# v1_control.net
KiCad netlist of a schematic drawn in Altium Designer
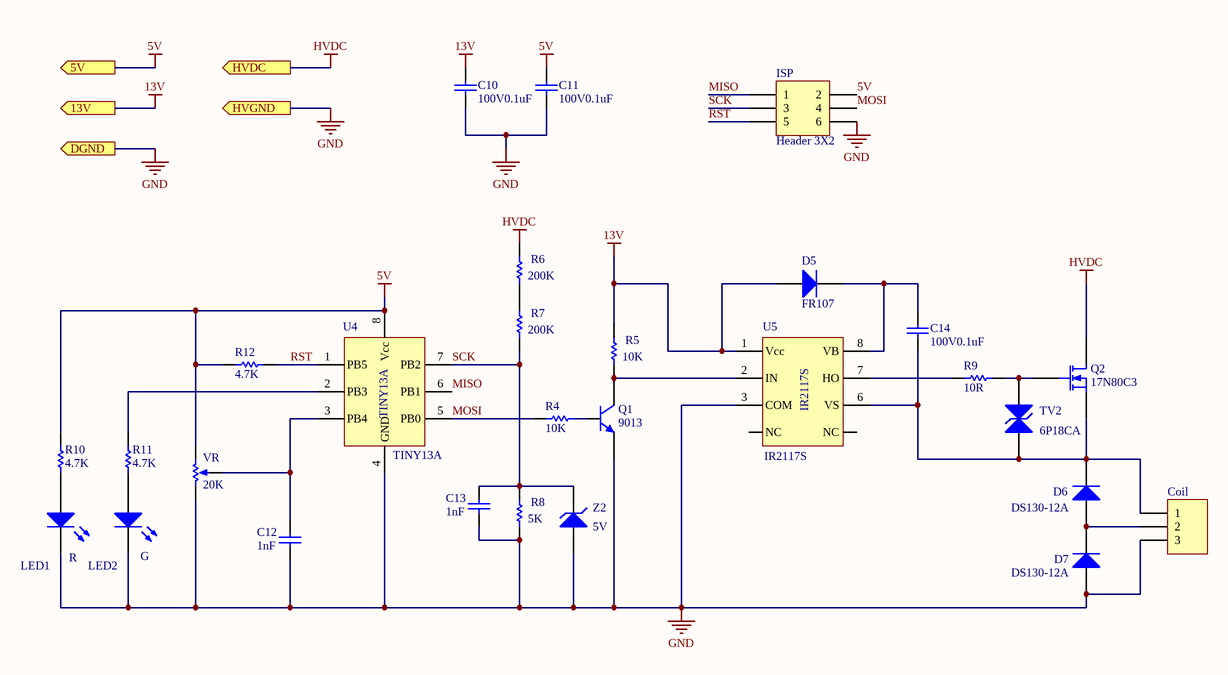
[diagram p0: v1_control.SCHDOC]

(export (version "E")
  (design (tool "Eeschema 10.0.6"))
  (components
    (comp (ref "C10")
      (value "100V0.1uF")
      (footprint "CAP6")
      (description "Capacitor")
      (fields (field (name "PUBLISHER") "Altium Limited"))
      (libsource (lib "magcontrol") (part "Cap"))
    )
    (comp (ref "C11")
      (value "100V0.1uF")
      (footprint "CAP6")
      (description "Capacitor")
      (fields (field (name "PUBLISHER") "Altium Limited"))
      (libsource (lib "magcontrol") (part "Cap"))
    )
    (comp (ref "C12")
      (value "1nF")
      (footprint "CAP6")
      (description "Capacitor")
      (fields (field (name "PUBLISHER") "Altium Limited"))
      (libsource (lib "magcontrol") (part "Cap"))
    )
    (comp (ref "C13")
      (value "1nF")
      (footprint "CAP6")
      (description "Capacitor")
      (fields (field (name "PUBLISHER") "Altium Limited"))
      (libsource (lib "magcontrol") (part "Cap"))
    )
    (comp (ref "C14")
      (value "100V0.1uF")
      (footprint "CAP6")
      (description "Capacitor")
      (fields (field (name "PUBLISHER") "Altium Limited"))
      (libsource (lib "magcontrol") (part "Cap"))
    )
    (comp (ref "Coil")
      (value "Header 3")
      (footprint "Terminal3_1")
      (description "Header, 3-Pin")
      (fields (field (name "PUBLISHER") "Altium Limited"))
      (libsource (lib "magcontrol") (part "Header 3"))
    )
    (comp (ref "D5")
      (value "FR107")
      (footprint "DIO1")
      (description "1 Amp Fast Recovery Rectifier")
      (fields (field (name "PUBLISHER") "Altium Limited"))
      (libsource (lib "magcontrol") (part "Diode"))
    )
    (comp (ref "D6")
      (value "DS130-12A")
      (footprint "TO-220_2")
      (description "Diode")
      (fields (field (name "PUBLISHER") "Altium Limited"))
      (libsource (lib "magcontrol") (part "Diode"))
    )
    (comp (ref "D7")
      (value "DS130-12A")
      (footprint "TO-220_2")
      (description "Diode")
      (fields (field (name "PUBLISHER") "Altium Limited"))
      (libsource (lib "magcontrol") (part "Diode"))
    )
    (comp (ref "ISP")
      (value "Header 3X2")
      (footprint "HDR2X3")
      (description "Header, 3-Pin, Dual row")
      (fields (field (name "PUBLISHER") "Altium Limited"))
      (libsource (lib "Miscellaneous Connectors") (part "Header 3X2"))
    )
    (comp (ref "LED1")
      (value "R")
      (footprint "LED1R")
      (description "LED")
      (fields (field (name "PUBLISHER") "Altium Limited"))
      (libsource (lib "magcontrol") (part "LED"))
    )
    (comp (ref "LED2")
      (value "G")
      (footprint "LED1G")
      (description "LED")
      (fields (field (name "PUBLISHER") "Altium Limited"))
      (libsource (lib "magcontrol") (part "LED"))
    )
    (comp (ref "Q1")
      (value "9013")
      (footprint "TO-92D")
      (description "NPN Bipolar Transistor")
      (fields (field (name "PUBLISHER") "Altium Limited"))
      (libsource (lib "magcontrol") (part "9013"))
    )
    (comp (ref "Q2")
      (value "17N80C3")
      (footprint "TO-247")
      (description "MOSFET N")
      (fields (field (name "PUBLISHER") "Altium Limited"))
      (libsource (lib "magcontrol") (part "17N80C3"))
    )
    (comp (ref "R4")
      (value "10K")
      (footprint "RES0.25W")
      (description "Resistor")
      (fields (field (name "PUBLISHER") "Altium Limited"))
      (libsource (lib "magcontrol") (part "Res1"))
    )
    (comp (ref "R5")
      (value "10K")
      (footprint "RES0.25W")
      (description "Resistor")
      (fields (field (name "PUBLISHER") "Altium Limited"))
      (libsource (lib "magcontrol") (part "Res1"))
    )
    (comp (ref "R6")
      (value "200K")
      (footprint "RES0.25W")
      (description "Resistor")
      (fields (field (name "PUBLISHER") "Altium Limited"))
      (libsource (lib "magcontrol") (part "Res1"))
    )
    (comp (ref "R7")
      (value "200K")
      (footprint "RES0.25W")
      (description "Resistor")
      (fields (field (name "PUBLISHER") "Altium Limited"))
      (libsource (lib "magcontrol") (part "Res1"))
    )
    (comp (ref "R8")
      (value "5K")
      (footprint "RES0.25W")
      (description "Resistor")
      (fields (field (name "PUBLISHER") "Altium Limited"))
      (libsource (lib "magcontrol") (part "Res1"))
    )
    (comp (ref "R9")
      (value "10R")
      (footprint "RES0.25W")
      (description "Resistor")
      (fields (field (name "PUBLISHER") "Altium Limited"))
      (libsource (lib "magcontrol") (part "Res1"))
    )
    (comp (ref "R10")
      (value "4.7K")
      (footprint "RES0.25W")
      (description "Resistor")
      (fields (field (name "PUBLISHER") "Altium Limited"))
      (libsource (lib "magcontrol") (part "Res1"))
    )
    (comp (ref "R11")
      (value "4.7K")
      (footprint "RES0.25W")
      (description "Resistor")
      (fields (field (name "PUBLISHER") "Altium Limited"))
      (libsource (lib "magcontrol") (part "Res1"))
    )
    (comp (ref "R12")
      (value "4.7K")
      (footprint "RES0.25W")
      (description "Resistor")
      (fields (field (name "PUBLISHER") "Altium Limited"))
      (libsource (lib "magcontrol") (part "Res1"))
    )
    (comp (ref "TV2")
      (value "6P18CA")
      (footprint "TVS2")
      (description "TVS Diode")
      (fields (field (name "PUBLISHER") "Altium Limited"))
      (libsource (lib "magcontrol") (part "TVS"))
    )
    (comp (ref "U4")
      (value "TINY13A")
      (footprint "DIP-8")
      (description "AVR MCU")
      (libsource (lib "magcontrol") (part "TINY13A"))
    )
    (comp (ref "U5")
      (value "IR2117S")
      (footprint "DIP-8")
      (description "MOSFET Driver")
      (libsource (lib "magcontrol") (part "IR2117S"))
    )
    (comp (ref "VR")
      (value "20K")
      (footprint "3296W")
      (description "Potentiometer")
      (fields (field (name "Comment") "RPot") (field (name "PUBLISHER") "Altium Limited"))
      (libsource (lib "magcontrol") (part "RPot"))
    )
    (comp (ref "Z2")
      (value "5V")
      (footprint "DIO2")
      (description "Zener Diode")
      (fields (field (name "PUBLISHER") "Altium Limited"))
      (libsource (lib "magcontrol") (part "D Zener"))
    )
  )
  (nets
    (net (code "1") (name "/MISO") (class "Default")
      (node (ref "ISP") (pin "1") (pinfunction "1_1") (pintype "passive"))
      (node (ref "U4") (pin "6") (pinfunction "PB1_6") (pintype "power_in"))
    )
    (net (code "2") (name "/MOSI") (class "Default")
      (node (ref "ISP") (pin "4") (pinfunction "4_4") (pintype "passive"))
      (node (ref "R4") (pin "2") (pinfunction "2_2") (pintype "passive"))
      (node (ref "U4") (pin "5") (pinfunction "PB0_5") (pintype "power_in"))
    )
    (net (code "3") (name "/RST") (class "Default")
      (node (ref "ISP") (pin "5") (pinfunction "5_5") (pintype "passive"))
      (node (ref "R12") (pin "2") (pinfunction "2_2") (pintype "passive"))
      (node (ref "U4") (pin "1") (pinfunction "PB5_1") (pintype "power_in"))
    )
    (net (code "4") (name "/SCK") (class "Default")
      (node (ref "C13") (pin "1") (pinfunction "1_1") (pintype "passive"))
      (node (ref "ISP") (pin "3") (pinfunction "3_3") (pintype "passive"))
      (node (ref "R7") (pin "2") (pinfunction "2_2") (pintype "passive"))
      (node (ref "R8") (pin "1") (pinfunction "1_1") (pintype "passive"))
      (node (ref "U4") (pin "7") (pinfunction "PB2_7") (pintype "power_in"))
      (node (ref "Z2") (pin "2") (pinfunction "K_2") (pintype "passive"))
    )
    (net (code "5") (name "5V") (class "Default")
      (node (ref "C11") (pin "1") (pinfunction "1_1") (pintype "passive"))
      (node (ref "ISP") (pin "2") (pinfunction "2_2") (pintype "passive"))
      (node (ref "R10") (pin "1") (pinfunction "1_1") (pintype "passive"))
      (node (ref "R12") (pin "1") (pinfunction "1_1") (pintype "passive"))
      (node (ref "U4") (pin "8") (pinfunction "Vcc_8") (pintype "power_in"))
      (node (ref "VR") (pin "1") (pinfunction "1_1") (pintype "passive"))
    )
    (net (code "6") (name "13V") (class "Default")
      (node (ref "C10") (pin "1") (pinfunction "1_1") (pintype "passive"))
      (node (ref "D5") (pin "1") (pinfunction "A_1") (pintype "passive"))
      (node (ref "R5") (pin "1") (pinfunction "1_1") (pintype "passive"))
      (node (ref "U5") (pin "1") (pinfunction "Vcc_1") (pintype "power_in"))
    )
    (net (code "7") (name "GND") (class "Default")
      (node (ref "C10") (pin "2") (pinfunction "2_2") (pintype "passive"))
      (node (ref "C11") (pin "2") (pinfunction "2_2") (pintype "passive"))
      (node (ref "C12") (pin "2") (pinfunction "2_2") (pintype "passive"))
      (node (ref "C13") (pin "2") (pinfunction "2_2") (pintype "passive"))
      (node (ref "Coil") (pin "3") (pinfunction "3_3") (pintype "passive"))
      (node (ref "D7") (pin "1") (pinfunction "A_1") (pintype "passive"))
      (node (ref "ISP") (pin "6") (pinfunction "6_6") (pintype "passive"))
      (node (ref "LED1") (pin "2") (pinfunction "K_2") (pintype "passive"))
      (node (ref "LED2") (pin "2") (pinfunction "K_2") (pintype "passive"))
      (node (ref "Q1") (pin "1") (pinfunction "E_1") (pintype "passive"))
      (node (ref "R8") (pin "2") (pinfunction "2_2") (pintype "passive"))
      (node (ref "U4") (pin "4") (pinfunction "GND_4") (pintype "power_in"))
      (node (ref "U5") (pin "3") (pinfunction "COM_3") (pintype "power_in"))
      (node (ref "VR") (pin "3") (pinfunction "3_3") (pintype "passive"))
      (node (ref "Z2") (pin "1") (pinfunction "A_1") (pintype "passive"))
    )
    (net (code "8") (name "HVDC") (class "Default")
      (node (ref "Q2") (pin "2") (pinfunction "D_2") (pintype "passive"))
      (node (ref "R6") (pin "1") (pinfunction "1_1") (pintype "passive"))
    )
    (net (code "9") (name "Net-(D5-K)") (class "Default")
      (node (ref "C14") (pin "1") (pinfunction "1_1") (pintype "passive"))
      (node (ref "D5") (pin "2") (pinfunction "K_2") (pintype "passive"))
      (node (ref "U5") (pin "8") (pinfunction "VB_8") (pintype "power_in"))
    )
    (net (code "10") (name "Net-(D6-A)") (class "Default")
      (node (ref "Coil") (pin "2") (pinfunction "2_2") (pintype "passive"))
      (node (ref "D6") (pin "1") (pinfunction "A_1") (pintype "passive"))
      (node (ref "D7") (pin "2") (pinfunction "K_2") (pintype "passive"))
    )
    (net (code "11") (name "Net-(D6-K)") (class "Default")
      (node (ref "C14") (pin "2") (pinfunction "2_2") (pintype "passive"))
      (node (ref "Coil") (pin "1") (pinfunction "1_1") (pintype "passive"))
      (node (ref "D6") (pin "2") (pinfunction "K_2") (pintype "passive"))
      (node (ref "Q2") (pin "3") (pinfunction "S_3") (pintype "passive"))
      (node (ref "TV2") (pin "1") (pinfunction "A_1") (pintype "passive"))
      (node (ref "U5") (pin "6") (pinfunction "VS_6") (pintype "power_in"))
    )
    (net (code "12") (name "Net-(LED1-A)") (class "Default")
      (node (ref "LED1") (pin "1") (pinfunction "A_1") (pintype "passive"))
      (node (ref "R10") (pin "2") (pinfunction "2_2") (pintype "passive"))
    )
    (net (code "13") (name "Net-(LED2-A)") (class "Default")
      (node (ref "LED2") (pin "1") (pinfunction "A_1") (pintype "passive"))
      (node (ref "R11") (pin "2") (pinfunction "2_2") (pintype "passive"))
    )
    (net (code "14") (name "Net-(Q1-B)") (class "Default")
      (node (ref "Q1") (pin "2") (pinfunction "B_2") (pintype "passive"))
      (node (ref "R4") (pin "1") (pinfunction "1_1") (pintype "passive"))
    )
    (net (code "15") (name "Net-(Q1-C)") (class "Default")
      (node (ref "Q1") (pin "3") (pinfunction "C_3") (pintype "passive"))
      (node (ref "R5") (pin "2") (pinfunction "2_2") (pintype "passive"))
      (node (ref "U5") (pin "2") (pinfunction "IN_2") (pintype "power_in"))
    )
    (net (code "16") (name "Net-(Q2-G)") (class "Default")
      (node (ref "Q2") (pin "1") (pinfunction "G_1") (pintype "passive"))
      (node (ref "R9") (pin "2") (pinfunction "2_2") (pintype "passive"))
      (node (ref "TV2") (pin "2") (pinfunction "K_2") (pintype "passive"))
    )
    (net (code "17") (name "Net-(R6-Pad2)") (class "Default")
      (node (ref "R6") (pin "2") (pinfunction "2_2") (pintype "passive"))
      (node (ref "R7") (pin "1") (pinfunction "1_1") (pintype "passive"))
    )
    (net (code "18") (name "Net-(U4-PB3)") (class "Default")
      (node (ref "R11") (pin "1") (pinfunction "1_1") (pintype "passive"))
      (node (ref "U4") (pin "2") (pinfunction "PB3_2") (pintype "power_in"))
    )
    (net (code "19") (name "Net-(U4-PB4)") (class "Default")
      (node (ref "C12") (pin "1") (pinfunction "1_1") (pintype "passive"))
      (node (ref "U4") (pin "3") (pinfunction "PB4_3") (pintype "power_in"))
      (node (ref "VR") (pin "2") (pinfunction "2_2") (pintype "passive"))
    )
    (net (code "20") (name "Net-(U5-HO)") (class "Default")
      (node (ref "R9") (pin "1") (pinfunction "1_1") (pintype "passive"))
      (node (ref "U5") (pin "7") (pinfunction "HO_7") (pintype "power_in"))
    )
    (net (code "21") (name "unconnected-(U5-NC-Pad4)") (class "Default")
      (node (ref "U5") (pin "4") (pinfunction "NC_4") (pintype "power_in"))
    )
    (net (code "22") (name "unconnected-(U5-NC-Pad5)") (class "Default")
      (node (ref "U5") (pin "5") (pinfunction "NC_5") (pintype "power_in"))
    )
  )
)
